# arduino_to_esp8266-01.net
KiCad netlist of a schematic drawn in EAGLE
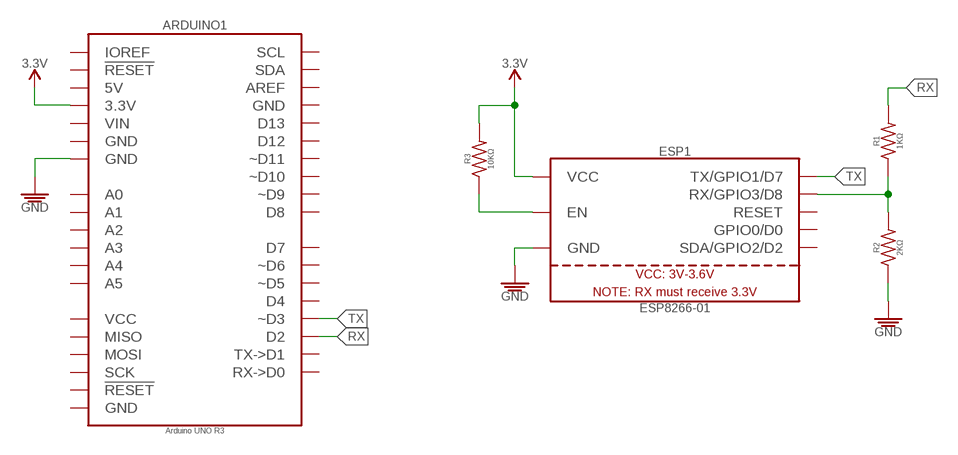
[diagram p0: schematic, sheet 1]

(export (version "E")
  (design (tool "Eeschema 10.0.6"))
  (components
    (comp (ref "ARDUINO1")
      (value "Arduino UNO R3")
      (footprint "eagle-import:ARDUINO_UNO_R3")
      (fields (field (name "MFR") "Arduino") (field (name "MPN") "A000066"))
      (libsource (lib "eagle-import") (part "ARDUINO_UNO_R3"))
    )
    (comp (ref "ESP1")
      (value "ESP8266-01")
      (footprint "eagle-import:ESP8266-01")
      (fields (field (name "MFR") "SparkFun Electronics") (field (name "MPN") "WRL-13678"))
      (libsource (lib "eagle-import") (part "ESP8266-01"))
    )
    (comp (ref "R1")
      (value "1KΩ")
      (footprint "eagle-import:RESISTOR-PTH-0207_7")
      (fields (field (name "CREATOR") "MrSwirlyEyes"))
      (libsource (lib "eagle-import") (part "1KΩ_PTH-0207/7_1/8W-5%"))
    )
    (comp (ref "R2")
      (value "2KΩ")
      (footprint "eagle-import:RESISTOR-PTH-0207_7")
      (fields (field (name "CREATOR") "MrSwirlyEyes"))
      (libsource (lib "eagle-import") (part "2KΩ_PTH-0207/7_1/8W-5%"))
    )
    (comp (ref "R3")
      (value "10KΩ")
      (footprint "eagle-import:RESISTOR-PTH-0207_7")
      (fields (field (name "CREATOR") "MrSwirlyEyes"))
      (libsource (lib "eagle-import") (part "10KΩ_PTH-0207/7_1/8W-5%"))
    )
  )
  (nets
    (net (code "1") (name "3.3V") (class "Default")
      (node (ref "ARDUINO1") (pin "3.3V") (pinfunction "3.3V_3.3V") (pintype "bidirectional"))
      (node (ref "ESP1") (pin "VCC") (pinfunction "VCC_VCC") (pintype "bidirectional"))
      (node (ref "R3") (pin "2") (pinfunction "2_2") (pintype "passive"))
    )
    (net (code "2") (name "GND") (class "Default")
      (node (ref "ARDUINO1") (pin "GND@3") (pinfunction "GND_GND@3") (pintype "bidirectional"))
      (node (ref "ESP1") (pin "GND") (pinfunction "GND_GND") (pintype "bidirectional"))
      (node (ref "R2") (pin "1") (pinfunction "1_1") (pintype "passive"))
    )
    (net (code "3") (name "Net-(ESP1-PadEN)") (class "Default")
      (node (ref "ESP1") (pin "EN") (pinfunction "EN_EN") (pintype "bidirectional"))
      (node (ref "R3") (pin "1") (pinfunction "1_1") (pintype "passive"))
    )
    (net (code "4") (name "Net-(ESP1-RX{slash}GPIO3{slash}D8)") (class "Default")
      (node (ref "ESP1") (pin "RX") (pinfunction "RX/GPIO3/D8_RX") (pintype "bidirectional"))
      (node (ref "R1") (pin "1") (pinfunction "1_1") (pintype "passive"))
      (node (ref "R2") (pin "2") (pinfunction "2_2") (pintype "passive"))
    )
    (net (code "5") (name "RX") (class "Default")
      (node (ref "ARDUINO1") (pin "D2") (pinfunction "D2_D2") (pintype "bidirectional"))
      (node (ref "R1") (pin "2") (pinfunction "2_2") (pintype "passive"))
    )
    (net (code "6") (name "TX") (class "Default")
      (node (ref "ARDUINO1") (pin "D3") (pinfunction "~{D3}_D3") (pintype "bidirectional"))
      (node (ref "ESP1") (pin "TX") (pinfunction "TX/GPIO1/D7_TX") (pintype "bidirectional"))
    )
    (net (code "7") (name "unconnected-(ARDUINO1-GND-PadGND@1)") (class "Default")
      (node (ref "ARDUINO1") (pin "GND@1") (pinfunction "GND_GND@1") (pintype "bidirectional"))
    )
    (net (code "8") (name "unconnected-(ARDUINO1-GND-PadGND@2)") (class "Default")
      (node (ref "ARDUINO1") (pin "GND@2") (pinfunction "GND_GND@2") (pintype "bidirectional"))
    )
    (net (code "9") (name "unconnected-(ARDUINO1-GND-PadGND@4)") (class "Default")
      (node (ref "ARDUINO1") (pin "GND@4") (pinfunction "GND_GND@4") (pintype "bidirectional"))
    )
    (net (code "10") (name "unconnected-(ARDUINO1-Pad5V)") (class "Default")
      (node (ref "ARDUINO1") (pin "5V") (pinfunction "5V_5V") (pintype "bidirectional"))
    )
    (net (code "11") (name "unconnected-(ARDUINO1-PadA0)") (class "Default")
      (node (ref "ARDUINO1") (pin "A0") (pinfunction "A0_A0") (pintype "bidirectional"))
    )
    (net (code "12") (name "unconnected-(ARDUINO1-PadA1)") (class "Default")
      (node (ref "ARDUINO1") (pin "A1") (pinfunction "A1_A1") (pintype "bidirectional"))
    )
    (net (code "13") (name "unconnected-(ARDUINO1-PadA2)") (class "Default")
      (node (ref "ARDUINO1") (pin "A2") (pinfunction "A2_A2") (pintype "bidirectional"))
    )
    (net (code "14") (name "unconnected-(ARDUINO1-PadA3)") (class "Default")
      (node (ref "ARDUINO1") (pin "A3") (pinfunction "A3_A3") (pintype "bidirectional"))
    )
    (net (code "15") (name "unconnected-(ARDUINO1-PadA4)") (class "Default")
      (node (ref "ARDUINO1") (pin "A4") (pinfunction "A4_A4") (pintype "bidirectional"))
    )
    (net (code "16") (name "unconnected-(ARDUINO1-PadA5)") (class "Default")
      (node (ref "ARDUINO1") (pin "A5") (pinfunction "A5_A5") (pintype "bidirectional"))
    )
    (net (code "17") (name "unconnected-(ARDUINO1-PadAREF)") (class "Default")
      (node (ref "ARDUINO1") (pin "AREF") (pinfunction "AREF_AREF") (pintype "bidirectional"))
    )
    (net (code "18") (name "unconnected-(ARDUINO1-PadD4)") (class "Default")
      (node (ref "ARDUINO1") (pin "D4") (pinfunction "D4_D4") (pintype "bidirectional"))
    )
    (net (code "19") (name "unconnected-(ARDUINO1-PadD7)") (class "Default")
      (node (ref "ARDUINO1") (pin "D7") (pinfunction "D7_D7") (pintype "bidirectional"))
    )
    (net (code "20") (name "unconnected-(ARDUINO1-PadD8)") (class "Default")
      (node (ref "ARDUINO1") (pin "D8") (pinfunction "D8_D8") (pintype "bidirectional"))
    )
    (net (code "21") (name "unconnected-(ARDUINO1-PadD12)") (class "Default")
      (node (ref "ARDUINO1") (pin "D12") (pinfunction "D12_D12") (pintype "bidirectional"))
    )
    (net (code "22") (name "unconnected-(ARDUINO1-PadD13)") (class "Default")
      (node (ref "ARDUINO1") (pin "D13") (pinfunction "D13_D13") (pintype "bidirectional"))
    )
    (net (code "23") (name "unconnected-(ARDUINO1-PadIOREF)") (class "Default")
      (node (ref "ARDUINO1") (pin "IOREF") (pinfunction "IOREF_IOREF") (pintype "bidirectional"))
    )
    (net (code "24") (name "unconnected-(ARDUINO1-PadMISO)") (class "Default")
      (node (ref "ARDUINO1") (pin "MISO") (pinfunction "MISO_MISO") (pintype "bidirectional"))
    )
    (net (code "25") (name "unconnected-(ARDUINO1-PadMOSI)") (class "Default")
      (node (ref "ARDUINO1") (pin "MOSI") (pinfunction "MOSI_MOSI") (pintype "bidirectional"))
    )
    (net (code "26") (name "unconnected-(ARDUINO1-PadSCK)") (class "Default")
      (node (ref "ARDUINO1") (pin "SCK") (pinfunction "SCK_SCK") (pintype "bidirectional"))
    )
    (net (code "27") (name "unconnected-(ARDUINO1-PadSCL)") (class "Default")
      (node (ref "ARDUINO1") (pin "SCL") (pinfunction "SCL_SCL") (pintype "bidirectional"))
    )
    (net (code "28") (name "unconnected-(ARDUINO1-PadSDA)") (class "Default")
      (node (ref "ARDUINO1") (pin "SDA") (pinfunction "SDA_SDA") (pintype "bidirectional"))
    )
    (net (code "29") (name "unconnected-(ARDUINO1-PadVCC)") (class "Default")
      (node (ref "ARDUINO1") (pin "VCC") (pinfunction "VCC_VCC") (pintype "bidirectional"))
    )
    (net (code "30") (name "unconnected-(ARDUINO1-PadVIN)") (class "Default")
      (node (ref "ARDUINO1") (pin "VIN") (pinfunction "VIN_VIN") (pintype "bidirectional"))
    )
    (net (code "31") (name "unconnected-(ARDUINO1-RX->D0-PadD0)") (class "Default")
      (node (ref "ARDUINO1") (pin "D0") (pinfunction "RX->D0_D0") (pintype "bidirectional"))
    )
    (net (code "32") (name "unconnected-(ARDUINO1-TX->D1-PadD1)") (class "Default")
      (node (ref "ARDUINO1") (pin "D1") (pinfunction "TX->D1_D1") (pintype "bidirectional"))
    )
    (net (code "33") (name "unconnected-(ARDUINO1-~{D5}-PadD5)") (class "Default")
      (node (ref "ARDUINO1") (pin "D5") (pinfunction "~{D5}_D5") (pintype "bidirectional"))
    )
    (net (code "34") (name "unconnected-(ARDUINO1-~{D6}-PadD6)") (class "Default")
      (node (ref "ARDUINO1") (pin "D6") (pinfunction "~{D6}_D6") (pintype "bidirectional"))
    )
    (net (code "35") (name "unconnected-(ARDUINO1-~{D9}-PadD9)") (class "Default")
      (node (ref "ARDUINO1") (pin "D9") (pinfunction "~{D9}_D9") (pintype "bidirectional"))
    )
    (net (code "36") (name "unconnected-(ARDUINO1-~{D10}-PadD10)") (class "Default")
      (node (ref "ARDUINO1") (pin "D10") (pinfunction "~{D10}_D10") (pintype "bidirectional"))
    )
    (net (code "37") (name "unconnected-(ARDUINO1-~{D11}-PadD11)") (class "Default")
      (node (ref "ARDUINO1") (pin "D11") (pinfunction "~{D11}_D11") (pintype "bidirectional"))
    )
    (net (code "38") (name "unconnected-(ARDUINO1-~{RESET}-PadRESET@1)") (class "Default")
      (node (ref "ARDUINO1") (pin "RESET@1") (pinfunction "~{RESET}_RESET@1") (pintype "bidirectional"))
    )
    (net (code "39") (name "unconnected-(ARDUINO1-~{RESET}-PadRESET@2)") (class "Default")
      (node (ref "ARDUINO1") (pin "RESET@2") (pinfunction "~{RESET}_RESET@2") (pintype "bidirectional"))
    )
    (net (code "40") (name "unconnected-(ESP1-GPIO0{slash}D0-PadGPIO0)") (class "Default")
      (node (ref "ESP1") (pin "GPIO0") (pinfunction "GPIO0/D0_GPIO0") (pintype "bidirectional"))
    )
    (net (code "41") (name "unconnected-(ESP1-PadRESET)") (class "Default")
      (node (ref "ESP1") (pin "RESET") (pinfunction "RESET_RESET") (pintype "bidirectional"))
    )
    (net (code "42") (name "unconnected-(ESP1-SDA{slash}GPIO2{slash}D2-PadGPIO2)") (class "Default")
      (node (ref "ESP1") (pin "GPIO2") (pinfunction "SDA/GPIO2/D2_GPIO2") (pintype "bidirectional"))
    )
  )
)
